# DSP_HUB75_and_Audio.net
KiCad netlist of a schematic drawn in EAGLE
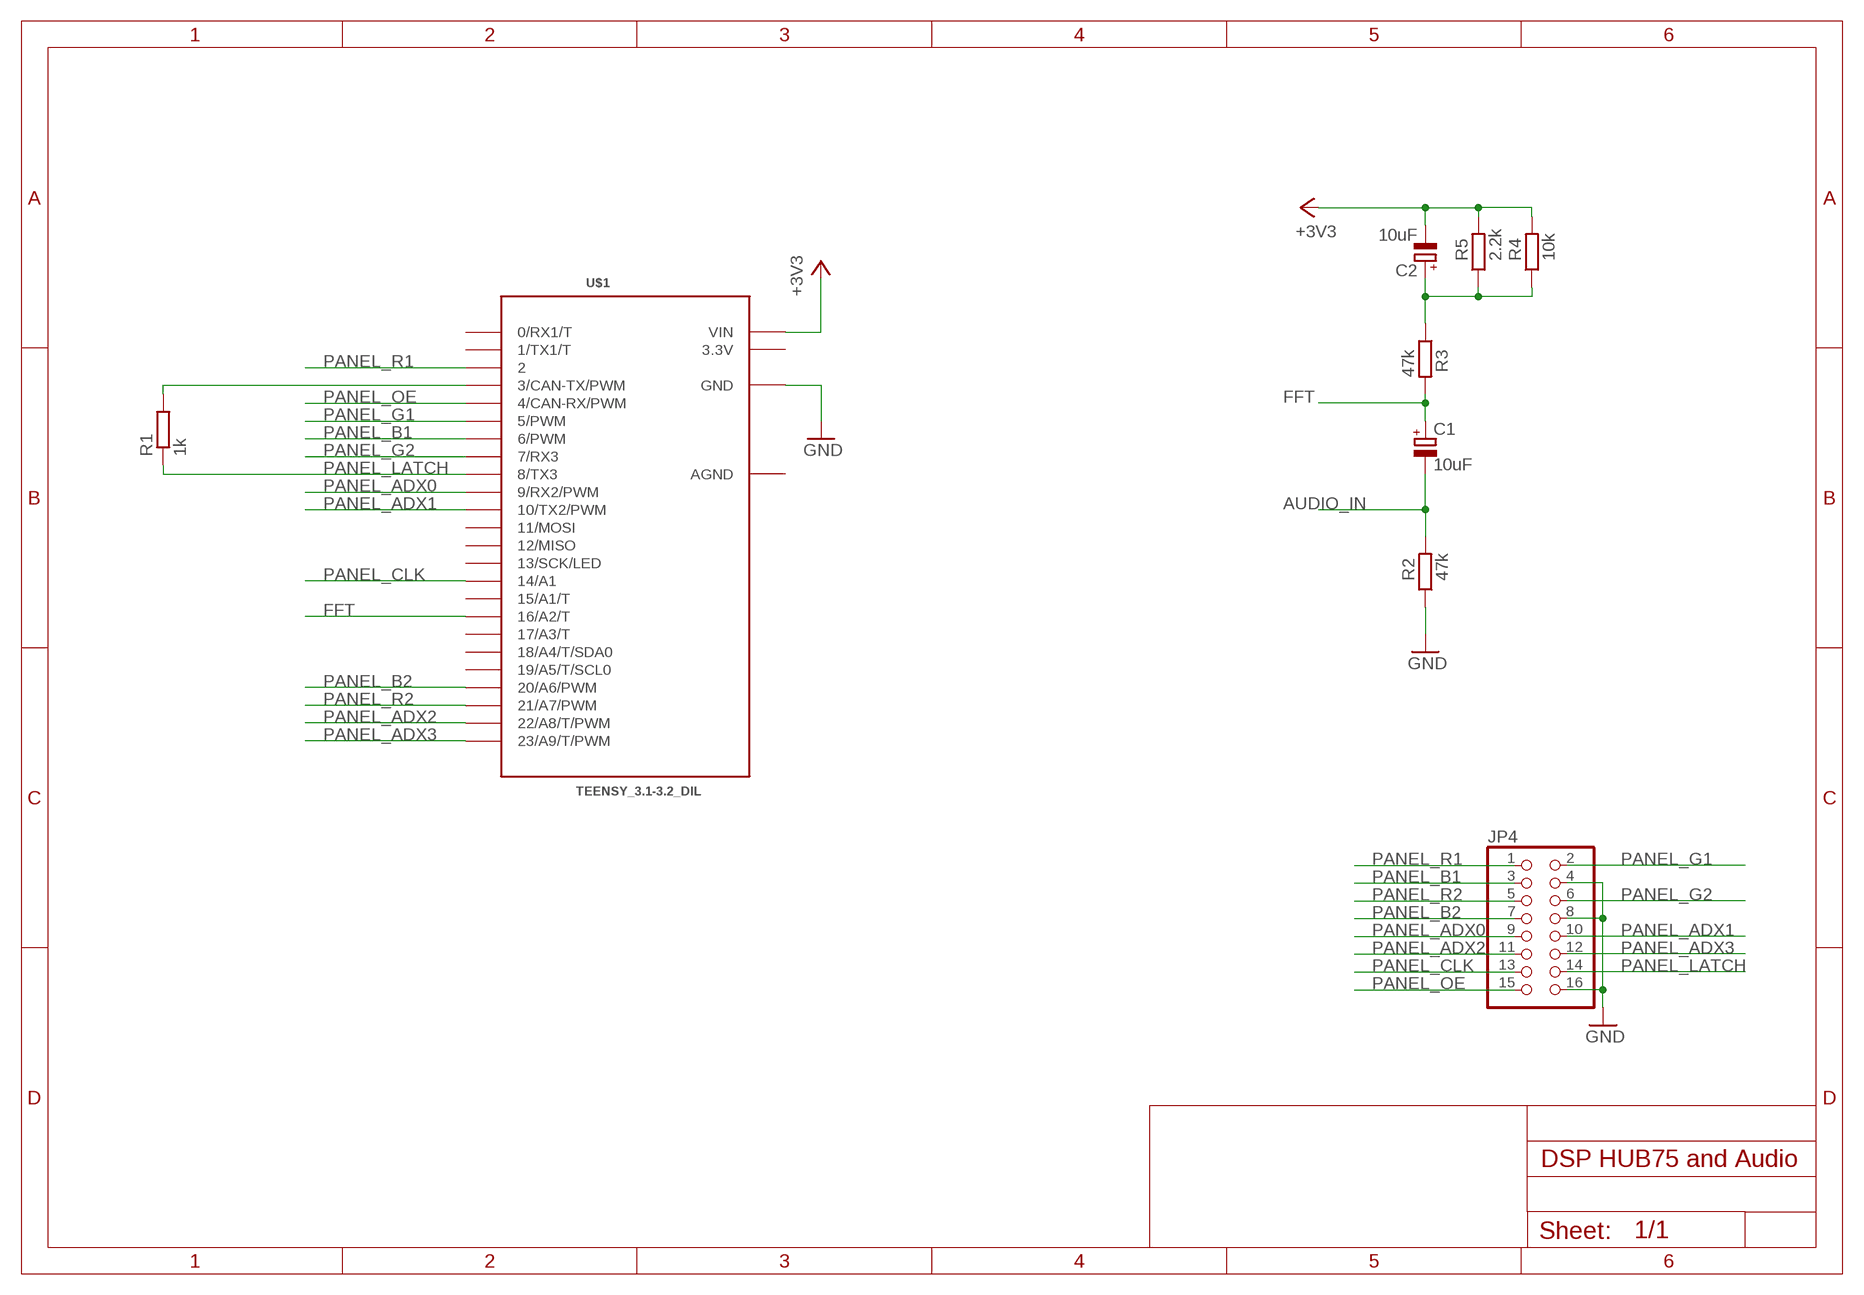
[diagram p0: schematic, sheet 1]

(export (version "E")
  (design (tool "Eeschema 10.0.6"))
  (components
    (comp (ref "C1")
      (value "10uF")
      (footprint "eagle-import:E1,8-4")
      (libsource (lib "eagle-import") (part "CPOL-EUE1.8-4"))
    )
    (comp (ref "C2")
      (value "10uF")
      (footprint "eagle-import:E1,8-4")
      (libsource (lib "eagle-import") (part "CPOL-EUE1.8-4"))
    )
    (comp (ref "JP4")
      (value "PINHD-2X08_2.54")
      (footprint "eagle-import:2X08")
      (libsource (lib "eagle-import") (part "PINHD-2X08_2.54"))
    )
    (comp (ref "R1")
      (value "1k")
      (footprint "eagle-import:0207_10")
      (libsource (lib "eagle-import") (part "R-EU_0207/10"))
    )
    (comp (ref "R2")
      (value "47k")
      (footprint "eagle-import:0207_10")
      (libsource (lib "eagle-import") (part "R-EU_0207/10"))
    )
    (comp (ref "R3")
      (value "47k")
      (footprint "eagle-import:0207_10")
      (libsource (lib "eagle-import") (part "R-EU_0207/10"))
    )
    (comp (ref "R4")
      (value "10k")
      (footprint "eagle-import:0207_10")
      (libsource (lib "eagle-import") (part "R-EU_0207/10"))
    )
    (comp (ref "R5")
      (value "2.2k")
      (footprint "eagle-import:0207_10")
      (libsource (lib "eagle-import") (part "R-EU_0207/10"))
    )
    (comp (ref "U$1")
      (value "TEENSY_3.1-3.2_DIL")
      (footprint "eagle-import:TEENSY_3.0-3.2&LC_DIL")
      (libsource (lib "eagle-import") (part "TEENSY_3.1-3.2_DIL"))
    )
  )
  (nets
    (net (code "1") (name "+3V3") (class "Default")
      (node (ref "C2") (pin "-") (pinfunction "-_-") (pintype "passive"))
      (node (ref "R4") (pin "2") (pinfunction "2_2") (pintype "passive"))
      (node (ref "R5") (pin "2") (pinfunction "2_2") (pintype "passive"))
      (node (ref "U$1") (pin "VIN") (pinfunction "VIN_VIN") (pintype "power_in"))
    )
    (net (code "2") (name "/3.3V") (class "Default")
      (node (ref "U$1") (pin "3.3V") (pinfunction "3.3V_3.3V") (pintype "power_in"))
    )
    (net (code "3") (name "/AGND") (class "Default")
      (node (ref "U$1") (pin "AGND") (pinfunction "AGND_AGND") (pintype "power_in"))
    )
    (net (code "4") (name "/AUDIO_IN") (class "Default")
      (node (ref "C1") (pin "-") (pinfunction "-_-") (pintype "passive"))
      (node (ref "R2") (pin "2") (pinfunction "2_2") (pintype "passive"))
    )
    (net (code "5") (name "/FFT") (class "Default")
      (node (ref "C1") (pin "+") (pinfunction "+_+") (pintype "passive"))
      (node (ref "R3") (pin "2") (pinfunction "2_2") (pintype "passive"))
      (node (ref "U$1") (pin "16/A2") (pinfunction "16/A2/T_16/A2") (pintype "bidirectional"))
    )
    (net (code "6") (name "/PANEL_ADX0") (class "Default")
      (node (ref "JP4") (pin "9") (pinfunction "9_9") (pintype "passive"))
      (node (ref "U$1") (pin "9") (pinfunction "9/RX2/PWM_9") (pintype "bidirectional"))
    )
    (net (code "7") (name "/PANEL_ADX1") (class "Default")
      (node (ref "JP4") (pin "10") (pinfunction "10_10") (pintype "passive"))
      (node (ref "U$1") (pin "10") (pinfunction "10/TX2/PWM_10") (pintype "bidirectional"))
    )
    (net (code "8") (name "/PANEL_ADX2") (class "Default")
      (node (ref "JP4") (pin "11") (pinfunction "11_11") (pintype "passive"))
      (node (ref "U$1") (pin "22/A8") (pinfunction "22/A8/T/PWM_22/A8") (pintype "bidirectional"))
    )
    (net (code "9") (name "/PANEL_ADX3") (class "Default")
      (node (ref "JP4") (pin "12") (pinfunction "12_12") (pintype "passive"))
      (node (ref "U$1") (pin "23/A9") (pinfunction "23/A9/T/PWM_23/A9") (pintype "bidirectional"))
    )
    (net (code "10") (name "/PANEL_B1") (class "Default")
      (node (ref "JP4") (pin "3") (pinfunction "3_3") (pintype "passive"))
      (node (ref "U$1") (pin "6") (pinfunction "6/PWM_6") (pintype "bidirectional"))
    )
    (net (code "11") (name "/PANEL_B2") (class "Default")
      (node (ref "JP4") (pin "7") (pinfunction "7_7") (pintype "passive"))
      (node (ref "U$1") (pin "20/A6") (pinfunction "20/A6/PWM_20/A6") (pintype "bidirectional"))
    )
    (net (code "12") (name "/PANEL_CLK") (class "Default")
      (node (ref "JP4") (pin "13") (pinfunction "13_13") (pintype "passive"))
      (node (ref "U$1") (pin "14/A0") (pinfunction "14/A1_14/A0") (pintype "bidirectional"))
    )
    (net (code "13") (name "/PANEL_G1") (class "Default")
      (node (ref "JP4") (pin "2") (pinfunction "2_2") (pintype "passive"))
      (node (ref "U$1") (pin "5") (pinfunction "5/PWM_5") (pintype "bidirectional"))
    )
    (net (code "14") (name "/PANEL_G2") (class "Default")
      (node (ref "JP4") (pin "6") (pinfunction "6_6") (pintype "passive"))
      (node (ref "U$1") (pin "7") (pinfunction "7/RX3_7") (pintype "bidirectional"))
    )
    (net (code "15") (name "/PANEL_LATCH") (class "Default")
      (node (ref "JP4") (pin "14") (pinfunction "14_14") (pintype "passive"))
      (node (ref "R1") (pin "1") (pinfunction "1_1") (pintype "passive"))
      (node (ref "U$1") (pin "8") (pinfunction "8/TX3_8") (pintype "bidirectional"))
    )
    (net (code "16") (name "/PANEL_OE") (class "Default")
      (node (ref "JP4") (pin "15") (pinfunction "15_15") (pintype "passive"))
      (node (ref "U$1") (pin "4") (pinfunction "4/CAN-RX/PWM_4") (pintype "bidirectional"))
    )
    (net (code "17") (name "/PANEL_R1") (class "Default")
      (node (ref "JP4") (pin "1") (pinfunction "1_1") (pintype "passive"))
      (node (ref "U$1") (pin "2") (pinfunction "2_2") (pintype "bidirectional"))
    )
    (net (code "18") (name "/PANEL_R2") (class "Default")
      (node (ref "JP4") (pin "5") (pinfunction "5_5") (pintype "passive"))
      (node (ref "U$1") (pin "21/A7") (pinfunction "21/A7/PWM_21/A7") (pintype "bidirectional"))
    )
    (net (code "19") (name "GND") (class "Default")
      (node (ref "JP4") (pin "16") (pinfunction "16_16") (pintype "passive"))
      (node (ref "JP4") (pin "4") (pinfunction "4_4") (pintype "passive"))
      (node (ref "JP4") (pin "8") (pinfunction "8_8") (pintype "passive"))
      (node (ref "R2") (pin "1") (pinfunction "1_1") (pintype "passive"))
      (node (ref "U$1") (pin "GND") (pinfunction "GND_GND") (pintype "power_in"))
    )
    (net (code "20") (name "Net-(C2-Pad+)") (class "Default")
      (node (ref "C2") (pin "+") (pinfunction "+_+") (pintype "passive"))
      (node (ref "R3") (pin "1") (pinfunction "1_1") (pintype "passive"))
      (node (ref "R4") (pin "1") (pinfunction "1_1") (pintype "passive"))
      (node (ref "R5") (pin "1") (pinfunction "1_1") (pintype "passive"))
    )
    (net (code "21") (name "Net-(U$1-3{slash}CAN-TX{slash}PWM)") (class "Default")
      (node (ref "R1") (pin "2") (pinfunction "2_2") (pintype "passive"))
      (node (ref "U$1") (pin "3") (pinfunction "3/CAN-TX/PWM_3") (pintype "bidirectional"))
    )
    (net (code "22") (name "unconnected-(U$1-0{slash}RX1{slash}T-Pad0)") (class "Default")
      (node (ref "U$1") (pin "0") (pinfunction "0/RX1/T_0") (pintype "bidirectional"))
    )
    (net (code "23") (name "unconnected-(U$1-1{slash}TX1{slash}T-Pad1)") (class "Default")
      (node (ref "U$1") (pin "1") (pinfunction "1/TX1/T_1") (pintype "bidirectional"))
    )
    (net (code "24") (name "unconnected-(U$1-11{slash}MOSI-Pad11)") (class "Default")
      (node (ref "U$1") (pin "11") (pinfunction "11/MOSI_11") (pintype "bidirectional"))
    )
    (net (code "25") (name "unconnected-(U$1-12{slash}MISO-Pad12)") (class "Default")
      (node (ref "U$1") (pin "12") (pinfunction "12/MISO_12") (pintype "bidirectional"))
    )
    (net (code "26") (name "unconnected-(U$1-13{slash}SCK{slash}LED-Pad13)") (class "Default")
      (node (ref "U$1") (pin "13") (pinfunction "13/SCK/LED_13") (pintype "bidirectional"))
    )
    (net (code "27") (name "unconnected-(U$1-15{slash}A1{slash}T-Pad15{slash}A1)") (class "Default")
      (node (ref "U$1") (pin "15/A1") (pinfunction "15/A1/T_15/A1") (pintype "bidirectional"))
    )
    (net (code "28") (name "unconnected-(U$1-17{slash}A3{slash}T-Pad17{slash}A3)") (class "Default")
      (node (ref "U$1") (pin "17/A3") (pinfunction "17/A3/T_17/A3") (pintype "bidirectional"))
    )
    (net (code "29") (name "unconnected-(U$1-18{slash}A4{slash}T{slash}SDA0-Pad18{slash}A4)") (class "Default")
      (node (ref "U$1") (pin "18/A4") (pinfunction "18/A4/T/SDA0_18/A4") (pintype "bidirectional"))
    )
    (net (code "30") (name "unconnected-(U$1-19{slash}A5{slash}T{slash}SCL0-Pad19{slash}A5)") (class "Default")
      (node (ref "U$1") (pin "19/A5") (pinfunction "19/A5/T/SCL0_19/A5") (pintype "bidirectional"))
    )
  )
)
